# AccelBreakout.net
KiCad netlist of a schematic drawn in EAGLE
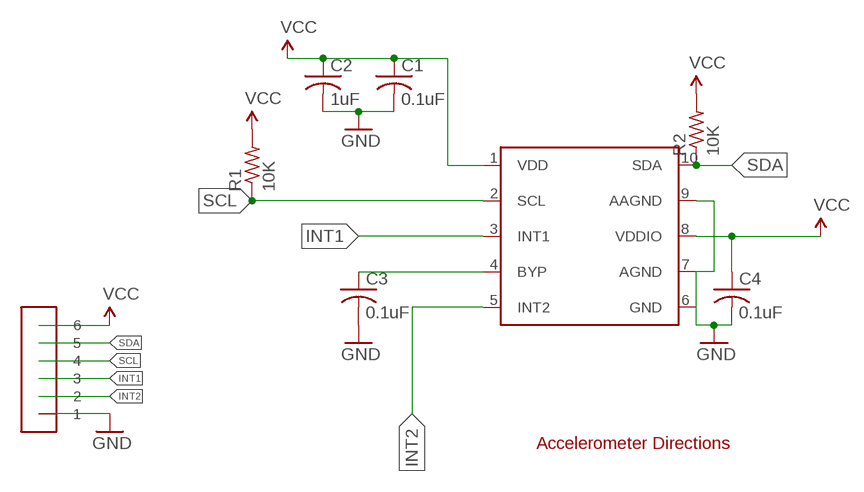
[diagram p0: schematic, sheet 1]

(export (version "E")
  (design (tool "Eeschema 10.0.6"))
  (components
    (comp (ref "C1")
      (value "0.1uF")
      (footprint "eagle-import:C0603")
      (libsource (lib "eagle-import") (part "C-USC0603"))
    )
    (comp (ref "C2")
      (value "1uF")
      (footprint "eagle-import:C0603")
      (libsource (lib "eagle-import") (part "C-USC0603"))
    )
    (comp (ref "C3")
      (value "0.1uF")
      (footprint "eagle-import:C0603")
      (libsource (lib "eagle-import") (part "C-USC0603"))
    )
    (comp (ref "C4")
      (value "0.1uF")
      (footprint "eagle-import:C0603")
      (libsource (lib "eagle-import") (part "C-USC0603"))
    )
    (comp (ref "R1")
      (value "10K")
      (footprint "eagle-import:R0603")
      (libsource (lib "eagle-import") (part "R-US_R0603"))
    )
    (comp (ref "R2")
      (value "10K")
      (footprint "eagle-import:R0603")
      (libsource (lib "eagle-import") (part "R-US_R0603"))
    )
    (comp (ref "U$1")
      (value "DIP1X6MALE")
      (footprint "eagle-import:DIP1X6MALE")
      (libsource (lib "eagle-import") (part "DIP1X6MALE"))
    )
    (comp (ref "U$2")
      (value "ACCELDIR")
      (footprint "eagle-import:ACCELDIR")
      (libsource (lib "eagle-import") (part "ACCELDIR"))
    )
    (comp (ref "U$23")
      (value "MMA8653FCR1")
      (footprint "eagle-import:MMA8653FCR1")
      (libsource (lib "eagle-import") (part "MMA8653FCR1"))
    )
  )
  (nets
    (net (code "1") (name "GND") (class "Default")
      (node (ref "C1") (pin "2") (pinfunction "2_2") (pintype "passive"))
      (node (ref "C2") (pin "2") (pinfunction "2_2") (pintype "passive"))
      (node (ref "C3") (pin "2") (pinfunction "2_2") (pintype "passive"))
      (node (ref "C4") (pin "2") (pinfunction "2_2") (pintype "passive"))
      (node (ref "U$1") (pin "1") (pinfunction "1_1") (pintype "bidirectional"))
      (node (ref "U$23") (pin "6") (pinfunction "GND_6") (pintype "bidirectional"))
      (node (ref "U$23") (pin "7") (pinfunction "AGND_7") (pintype "bidirectional"))
      (node (ref "U$23") (pin "9") (pinfunction "AAGND_9") (pintype "bidirectional"))
    )
    (net (code "2") (name "INT1") (class "Default")
      (node (ref "U$1") (pin "3") (pinfunction "3_3") (pintype "bidirectional"))
      (node (ref "U$23") (pin "3") (pinfunction "INT1_3") (pintype "bidirectional"))
    )
    (net (code "3") (name "INT2") (class "Default")
      (node (ref "U$1") (pin "2") (pinfunction "2_2") (pintype "bidirectional"))
      (node (ref "U$23") (pin "5") (pinfunction "INT2_5") (pintype "bidirectional"))
    )
    (net (code "4") (name "Net-(U$23-BYP)") (class "Default")
      (node (ref "C3") (pin "1") (pinfunction "1_1") (pintype "passive"))
      (node (ref "U$23") (pin "4") (pinfunction "BYP_4") (pintype "bidirectional"))
    )
    (net (code "5") (name "SCL") (class "Default")
      (node (ref "R1") (pin "1") (pinfunction "1_1") (pintype "passive"))
      (node (ref "U$1") (pin "4") (pinfunction "4_4") (pintype "bidirectional"))
      (node (ref "U$23") (pin "2") (pinfunction "SCL_2") (pintype "bidirectional"))
    )
    (net (code "6") (name "SDA") (class "Default")
      (node (ref "R2") (pin "1") (pinfunction "1_1") (pintype "passive"))
      (node (ref "U$1") (pin "5") (pinfunction "5_5") (pintype "bidirectional"))
      (node (ref "U$23") (pin "10") (pinfunction "SDA_10") (pintype "bidirectional"))
    )
    (net (code "7") (name "VCC") (class "Default")
      (node (ref "C1") (pin "1") (pinfunction "1_1") (pintype "passive"))
      (node (ref "C2") (pin "1") (pinfunction "1_1") (pintype "passive"))
      (node (ref "C4") (pin "1") (pinfunction "1_1") (pintype "passive"))
      (node (ref "R1") (pin "2") (pinfunction "2_2") (pintype "passive"))
      (node (ref "R2") (pin "2") (pinfunction "2_2") (pintype "passive"))
      (node (ref "U$1") (pin "6") (pinfunction "6_6") (pintype "bidirectional"))
      (node (ref "U$23") (pin "1") (pinfunction "VDD_1") (pintype "bidirectional"))
      (node (ref "U$23") (pin "8") (pinfunction "VDDIO_8") (pintype "bidirectional"))
    )
  )
)
